# HMD_Button.net
KiCad netlist of a schematic drawn in Altium Designer
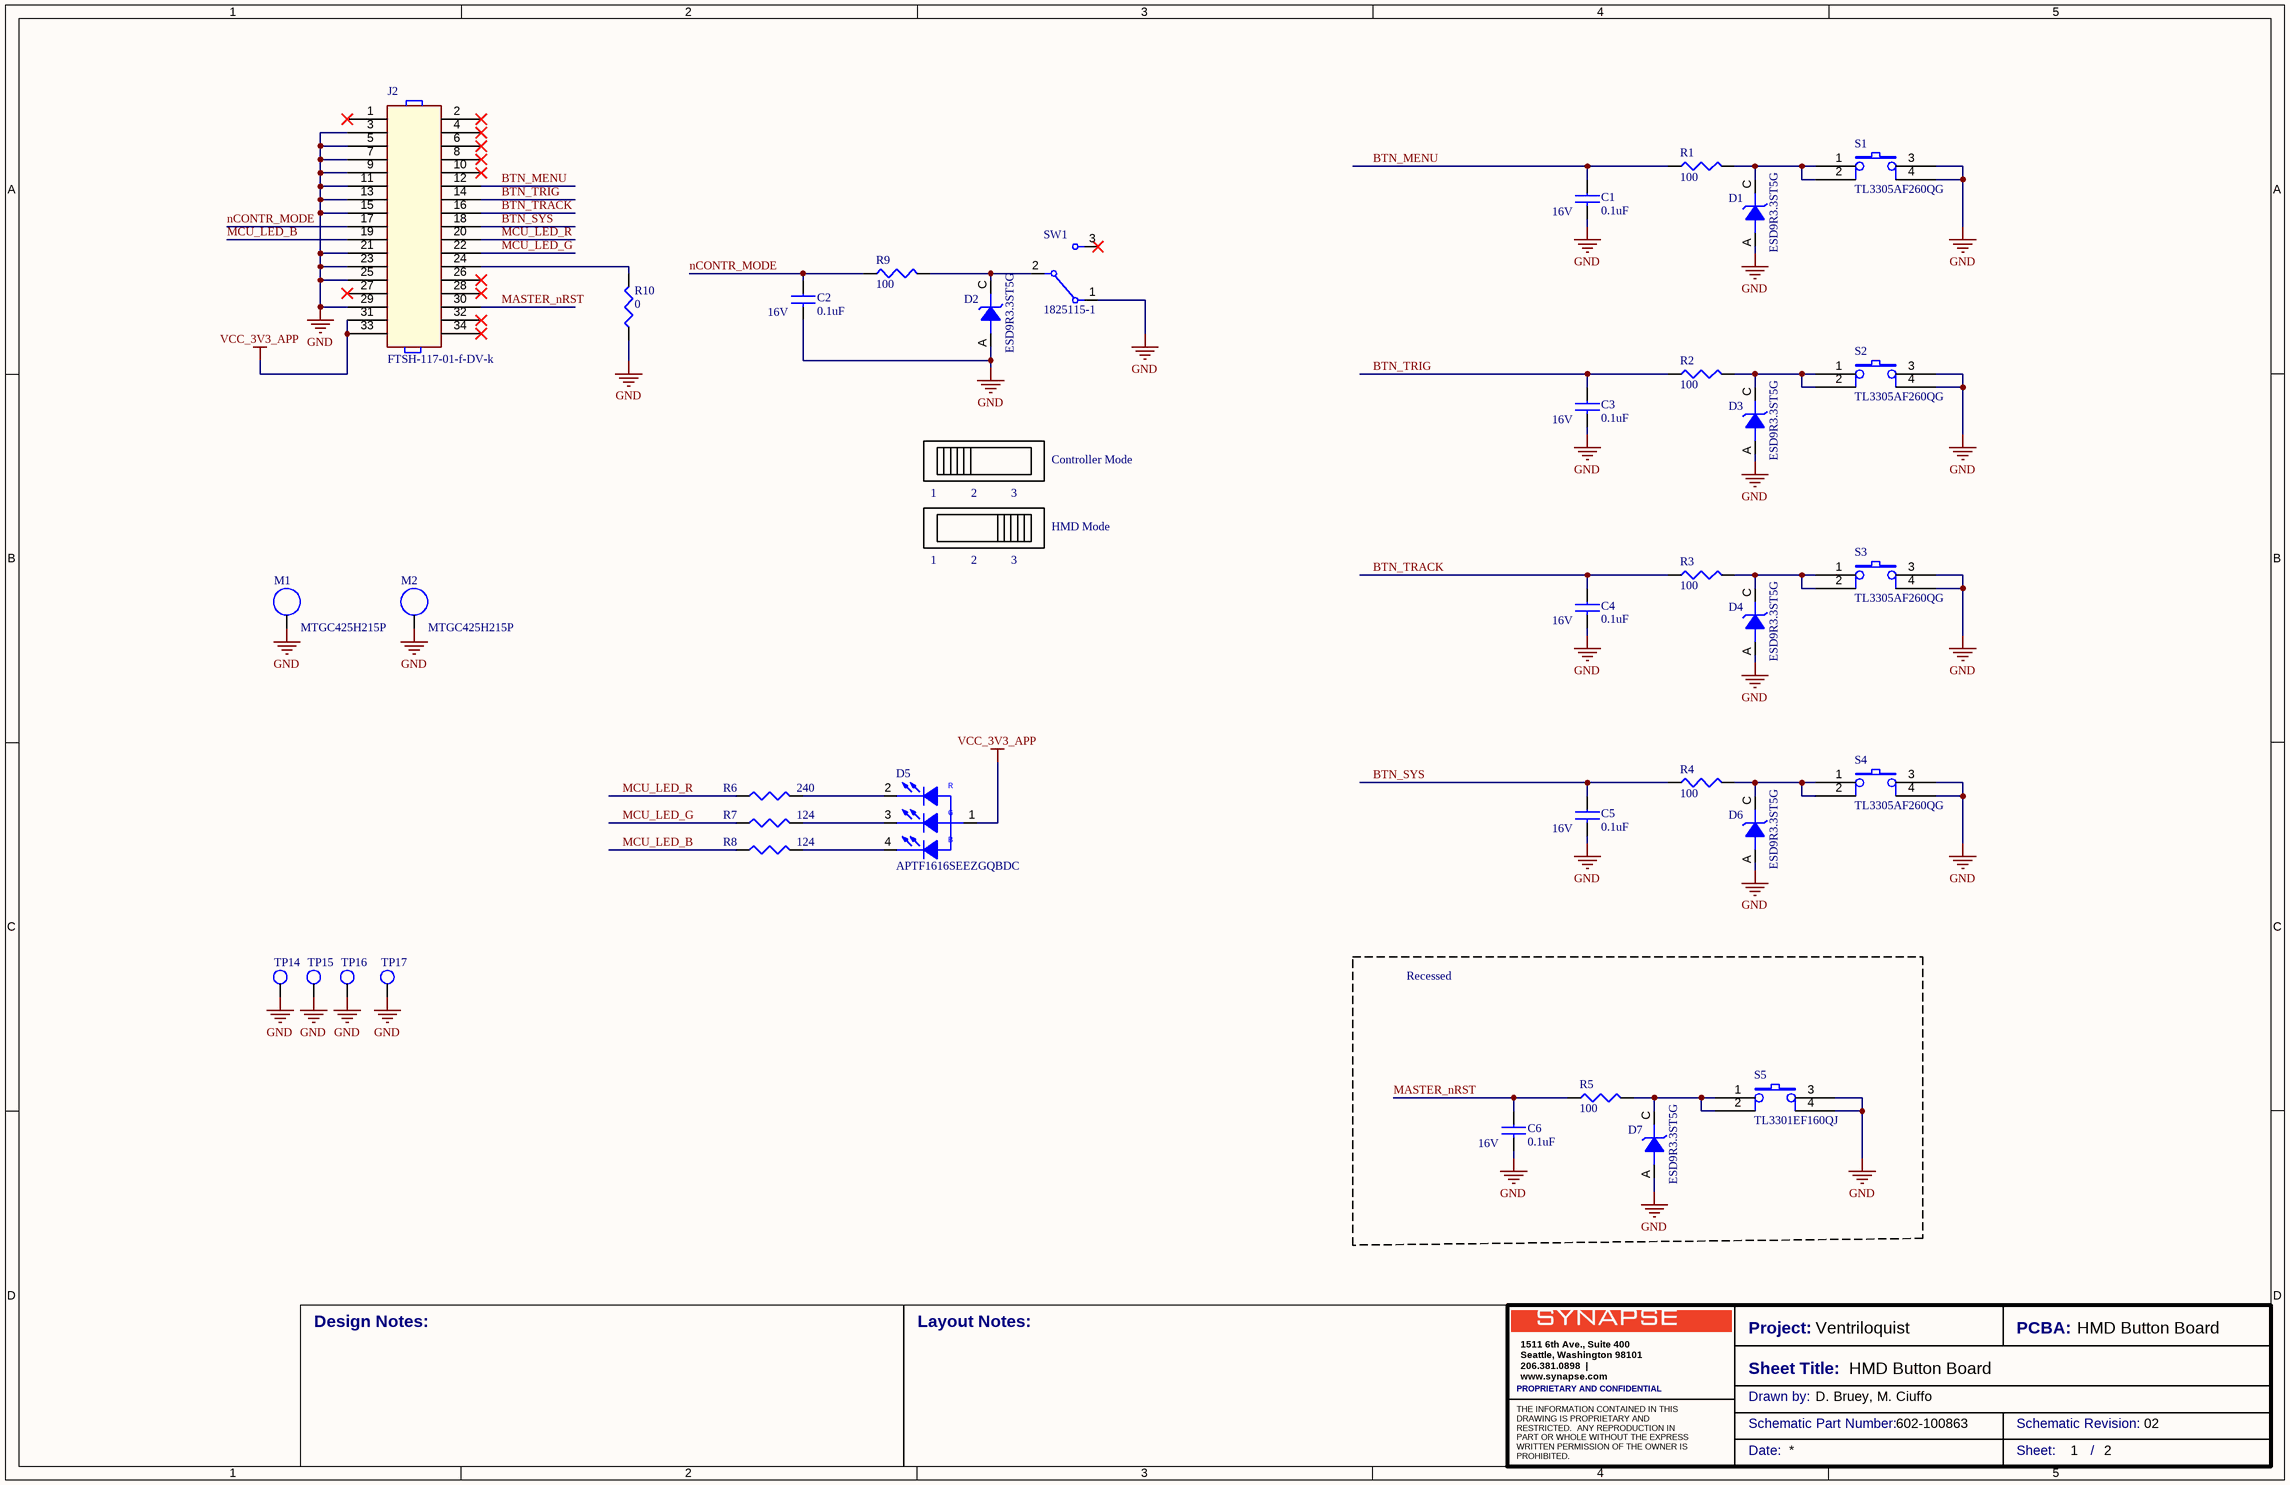
[diagram p0: HMD_Button.SchDoc]

(export (version "E")
  (design (tool "Eeschema 10.0.6"))
  (components
    (comp (ref "C1")
      (value "0.1uF")
      (footprint "0402-IPCsm_55")
      (description "CAP CER .1UF 16V X7R 0402")
      (fields (field (name "VOLTAGE") "16V") (field (name "MFG") "MURATA") (field (name "TOLERANCE") "10%"))
      (libsource (lib "SynapseLibrary") (part "CAP"))
    )
    (comp (ref "C2")
      (value "0.1uF")
      (footprint "0402-IPCsm_55")
      (description "CAP CER .1UF 16V X7R 0402")
      (fields (field (name "VOLTAGE") "16V") (field (name "MFG") "MURATA") (field (name "TOLERANCE") "10%"))
      (libsource (lib "SynapseLibrary") (part "CAP"))
    )
    (comp (ref "C3")
      (value "0.1uF")
      (footprint "0402-IPCsm_55")
      (description "CAP CER .1UF 16V X7R 0402")
      (fields (field (name "VOLTAGE") "16V") (field (name "MFG") "MURATA") (field (name "TOLERANCE") "10%"))
      (libsource (lib "SynapseLibrary") (part "CAP"))
    )
    (comp (ref "C4")
      (value "0.1uF")
      (footprint "0402-IPCsm_55")
      (description "CAP CER .1UF 16V X7R 0402")
      (fields (field (name "VOLTAGE") "16V") (field (name "MFG") "MURATA") (field (name "TOLERANCE") "10%"))
      (libsource (lib "SynapseLibrary") (part "CAP"))
    )
    (comp (ref "C5")
      (value "0.1uF")
      (footprint "0402-IPCsm_55")
      (description "CAP CER .1UF 16V X7R 0402")
      (fields (field (name "VOLTAGE") "16V") (field (name "MFG") "MURATA") (field (name "TOLERANCE") "10%"))
      (libsource (lib "SynapseLibrary") (part "CAP"))
    )
    (comp (ref "C6")
      (value "0.1uF")
      (footprint "0402-IPCsm_55")
      (description "CAP CER .1UF 16V X7R 0402")
      (fields (field (name "VOLTAGE") "16V") (field (name "MFG") "MURATA") (field (name "TOLERANCE") "10%"))
      (libsource (lib "SynapseLibrary") (part "CAP"))
    )
    (comp (ref "D1")
      (value "ESD9R3.3ST5G")
      (footprint "sod923-40")
      (description "TVS DIODE 3.3VWM 7.8VC SOD923")
      (fields (field (name "MFG") "On Semiconductor") (field (name "VOLTAGE") "3.3V"))
      (libsource (lib "SynapseLibrary") (part "TVS_UNI"))
    )
    (comp (ref "D2")
      (value "ESD9R3.3ST5G")
      (footprint "sod923-40")
      (description "TVS DIODE 3.3VWM 7.8VC SOD923")
      (fields (field (name "MFG") "On Semiconductor") (field (name "VOLTAGE") "3.3V"))
      (libsource (lib "SynapseLibrary") (part "TVS_UNI"))
    )
    (comp (ref "D3")
      (value "ESD9R3.3ST5G")
      (footprint "sod923-40")
      (description "TVS DIODE 3.3VWM 7.8VC SOD923")
      (fields (field (name "MFG") "On Semiconductor") (field (name "VOLTAGE") "3.3V"))
      (libsource (lib "SynapseLibrary") (part "TVS_UNI"))
    )
    (comp (ref "D4")
      (value "ESD9R3.3ST5G")
      (footprint "sod923-40")
      (description "TVS DIODE 3.3VWM 7.8VC SOD923")
      (fields (field (name "MFG") "On Semiconductor") (field (name "VOLTAGE") "3.3V"))
      (libsource (lib "SynapseLibrary") (part "TVS_UNI"))
    )
    (comp (ref "D5")
      (value "APTF1616SEEZGQBDC")
      (footprint "led_RBG_1p6x1p6_sm")
      (description "LED RGB CLEAR 0606 SMD")
      (fields (field (name "MFG") "Kingbright"))
      (libsource (lib "SynapseLibrary") (part "RGB_CA_HT-B3053FCH"))
    )
    (comp (ref "D6")
      (value "ESD9R3.3ST5G")
      (footprint "sod923-40")
      (description "TVS DIODE 3.3VWM 7.8VC SOD923")
      (fields (field (name "MFG") "On Semiconductor") (field (name "VOLTAGE") "3.3V"))
      (libsource (lib "SynapseLibrary") (part "TVS_UNI"))
    )
    (comp (ref "D7")
      (value "ESD9R3.3ST5G")
      (footprint "sod923-40")
      (description "TVS DIODE 3.3VWM 7.8VC SOD923")
      (fields (field (name "MFG") "On Semiconductor") (field (name "VOLTAGE") "3.3V"))
      (libsource (lib "SynapseLibrary") (part "TVS_UNI"))
    )
    (comp (ref "J2")
      (value "FTSH-117-01-f-DV-k")
      (footprint "FTSH-117-01-XXX-DV-K")
      (description "34 Positions Header, Shrouded Connector 0.050\" (1.27mm) Surface Mount Gold")
      (fields (field (name "MFG") "Samtec"))
      (libsource (lib "SynapseLibrary") (part "HEADER 17X2"))
    )
    (comp (ref "M1")
      (value "MTGC425H215P")
      (footprint "MTGC425H215P")
      (description "MTG, 4.25mm PAD, 2.15mm Plated Hole")
      (libsource (lib "SynapseLibrary") (part "MTG"))
    )
    (comp (ref "M2")
      (value "MTGC425H215P")
      (footprint "MTGC425H215P")
      (description "MTG, 4.25mm PAD, 2.15mm Plated Hole")
      (libsource (lib "SynapseLibrary") (part "MTG"))
    )
    (comp (ref "R1")
      (value "100")
      (footprint "0402-IPCsm_40")
      (description "RES 100 OHM 5% 0402 SMD")
      (fields (field (name "TOLERANCE") "5.00%") (field (name "MFG") "ROHM"))
      (libsource (lib "SynapseLibrary") (part "RES"))
    )
    (comp (ref "R2")
      (value "100")
      (footprint "0402-IPCsm_40")
      (description "RES 100 OHM 5% 0402 SMD")
      (fields (field (name "TOLERANCE") "5.00%") (field (name "MFG") "ROHM"))
      (libsource (lib "SynapseLibrary") (part "RES"))
    )
    (comp (ref "R3")
      (value "100")
      (footprint "0402-IPCsm_40")
      (description "RES 100 OHM 5% 0402 SMD")
      (fields (field (name "TOLERANCE") "5.00%") (field (name "MFG") "ROHM"))
      (libsource (lib "SynapseLibrary") (part "RES"))
    )
    (comp (ref "R4")
      (value "100")
      (footprint "0402-IPCsm_40")
      (description "RES 100 OHM 5% 0402 SMD")
      (fields (field (name "TOLERANCE") "5.00%") (field (name "MFG") "ROHM"))
      (libsource (lib "SynapseLibrary") (part "RES"))
    )
    (comp (ref "R5")
      (value "100")
      (footprint "0402-IPCsm_40")
      (description "RES 100 OHM 5% 0402 SMD")
      (fields (field (name "TOLERANCE") "5.00%") (field (name "MFG") "ROHM"))
      (libsource (lib "SynapseLibrary") (part "RES"))
    )
    (comp (ref "R6")
      (value "240")
      (footprint "0402-IPCsm_40")
      (description "RES 240 OHM 1/10W 1% 0402 SMD")
      (fields (field (name "TOLERANCE") "1%") (field (name "MFG") "Panasonic"))
      (libsource (lib "SynapseLibrary") (part "RES"))
    )
    (comp (ref "R7")
      (value "124")
      (footprint "0402-IPCsm_40")
      (description "RES SMD 124 OHM 1% 1/16W 0402")
      (fields (field (name "TOLERANCE") "1.00%") (field (name "MFG") "Yageo"))
      (libsource (lib "SynapseLibrary") (part "RES"))
    )
    (comp (ref "R8")
      (value "124")
      (footprint "0402-IPCsm_40")
      (description "RES SMD 124 OHM 1% 1/16W 0402")
      (fields (field (name "TOLERANCE") "1.00%") (field (name "MFG") "Yageo"))
      (libsource (lib "SynapseLibrary") (part "RES"))
    )
    (comp (ref "R9")
      (value "100")
      (footprint "0402-IPCsm_40")
      (description "RES 100 OHM 5% 0402 SMD")
      (fields (field (name "TOLERANCE") "5.00%") (field (name "MFG") "ROHM"))
      (libsource (lib "SynapseLibrary") (part "RES"))
    )
    (comp (ref "R10")
      (value "0")
      (footprint "0402-IPCsm_40")
      (description "RES 0.0 OHM 1/10W JUMP 0402 SMD")
      (fields (field (name "TOLERANCE") "5.00%") (field (name "MFG") "PANASONIC"))
      (libsource (lib "SynapseLibrary") (part "RES"))
    )
    (comp (ref "S1")
      (value "TL3305AF260QG")
      (footprint "SW_TL3305_G")
      (description "SWITCH TACTILE SPST-NO 50MA 12V")
      (fields (field (name "PART NUMBER") "TL3301AF260QG") (field (name "MANUFACTURER") "E-Switch"))
      (libsource (lib "SynapseLibrary") (part "ESWITCH_TL3301AF"))
    )
    (comp (ref "S2")
      (value "TL3305AF260QG")
      (footprint "SW_TL3305_G")
      (description "SWITCH TACTILE SPST-NO 50MA 12V")
      (fields (field (name "PART NUMBER") "TL3301AF260QG") (field (name "MANUFACTURER") "E-Switch"))
      (libsource (lib "SynapseLibrary") (part "ESWITCH_TL3301AF"))
    )
    (comp (ref "S3")
      (value "TL3305AF260QG")
      (footprint "SW_TL3305_G")
      (description "SWITCH TACTILE SPST-NO 50MA 12V")
      (fields (field (name "PART NUMBER") "TL3301AF260QG") (field (name "MANUFACTURER") "E-Switch"))
      (libsource (lib "SynapseLibrary") (part "ESWITCH_TL3301AF"))
    )
    (comp (ref "S4")
      (value "TL3305AF260QG")
      (footprint "SW_TL3305_G")
      (description "SWITCH TACTILE SPST-NO 50MA 12V")
      (fields (field (name "PART NUMBER") "TL3301AF260QG") (field (name "MANUFACTURER") "E-Switch"))
      (libsource (lib "SynapseLibrary") (part "ESWITCH_TL3301AF"))
    )
    (comp (ref "S5")
      (value "TL3301EF160QJ")
      (footprint "SW_TL3301_J")
      (description "SWITCH TACTILE SPST-NO 0.05A 12V")
      (fields (field (name "PART NUMBER") "TL3301AF260QG") (field (name "MANUFACTURER") "E-Switch"))
      (libsource (lib "SynapseLibrary") (part "ESWITCH_TL3301AF"))
    )
    (comp (ref "SW1")
      (value "1825115-1")
      (footprint "SW_3_TE_1825115")
      (description "SWITCH SLIDE SPDT 250MA 125V")
      (fields (field (name "MFG") "TE Connectivity"))
      (libsource (lib "SynapseLibrary") (part "SW_SLIDE_SPDT"))
    )
    (comp (ref "TP14")
      (value "tp-1mm")
      (footprint "TP-S100_SMT")
      (description "TESTPOINT, 1MM SMD, Square pad, Round SM opening")
      (fields (field (name "MFG") "NA"))
      (libsource (lib "SynapseLibrary") (part "tp_smt"))
    )
    (comp (ref "TP15")
      (value "tp-1mm")
      (footprint "TP-S100_SMT")
      (description "TESTPOINT, 1MM SMD, Square pad, Round SM opening")
      (fields (field (name "MFG") "NA"))
      (libsource (lib "SynapseLibrary") (part "tp_smt"))
    )
    (comp (ref "TP16")
      (value "tp-1mm")
      (footprint "TP-S100_SMT")
      (description "TESTPOINT, 1MM SMD, Square pad, Round SM opening")
      (fields (field (name "MFG") "NA"))
      (libsource (lib "SynapseLibrary") (part "tp_smt"))
    )
    (comp (ref "TP17")
      (value "tp-1mm")
      (footprint "TP-S100_SMT")
      (description "TESTPOINT, 1MM SMD, Square pad, Round SM opening")
      (fields (field (name "MFG") "NA"))
      (libsource (lib "SynapseLibrary") (part "tp_smt"))
    )
  )
  (nets
    (net (code "1") (name "/BTN_MENU") (class "Default")
      (node (ref "C1") (pin "1") (pinfunction "1_1") (pintype "passive"))
      (node (ref "J2") (pin "12") (pinfunction "12_12") (pintype "passive"))
      (node (ref "R1") (pin "1") (pinfunction "1_1") (pintype "passive"))
    )
    (net (code "2") (name "/BTN_SYS") (class "Default")
      (node (ref "C5") (pin "1") (pinfunction "1_1") (pintype "passive"))
      (node (ref "J2") (pin "18") (pinfunction "18_18") (pintype "passive"))
      (node (ref "R4") (pin "1") (pinfunction "1_1") (pintype "passive"))
    )
    (net (code "3") (name "/BTN_TRACK") (class "Default")
      (node (ref "C4") (pin "1") (pinfunction "1_1") (pintype "passive"))
      (node (ref "J2") (pin "16") (pinfunction "16_16") (pintype "passive"))
      (node (ref "R3") (pin "1") (pinfunction "1_1") (pintype "passive"))
    )
    (net (code "4") (name "/BTN_TRIG") (class "Default")
      (node (ref "C3") (pin "1") (pinfunction "1_1") (pintype "passive"))
      (node (ref "J2") (pin "14") (pinfunction "14_14") (pintype "passive"))
      (node (ref "R2") (pin "1") (pinfunction "1_1") (pintype "passive"))
    )
    (net (code "5") (name "/MASTER_nRST") (class "Default")
      (node (ref "C6") (pin "1") (pinfunction "1_1") (pintype "passive"))
      (node (ref "J2") (pin "30") (pinfunction "30_30") (pintype "passive"))
      (node (ref "R5") (pin "1") (pinfunction "1_1") (pintype "passive"))
    )
    (net (code "6") (name "/MCU_LED_B") (class "Default")
      (node (ref "J2") (pin "19") (pinfunction "19_19") (pintype "passive"))
      (node (ref "R8") (pin "1") (pinfunction "1_1") (pintype "passive"))
    )
    (net (code "7") (name "/MCU_LED_G") (class "Default")
      (node (ref "J2") (pin "22") (pinfunction "22_22") (pintype "passive"))
      (node (ref "R7") (pin "1") (pinfunction "1_1") (pintype "passive"))
    )
    (net (code "8") (name "/MCU_LED_R") (class "Default")
      (node (ref "J2") (pin "20") (pinfunction "20_20") (pintype "passive"))
      (node (ref "R6") (pin "1") (pinfunction "1_1") (pintype "passive"))
    )
    (net (code "9") (name "/nCONTR_MODE") (class "Default")
      (node (ref "C2") (pin "1") (pinfunction "1_1") (pintype "passive"))
      (node (ref "J2") (pin "17") (pinfunction "17_17") (pintype "passive"))
      (node (ref "R9") (pin "1") (pinfunction "1_1") (pintype "passive"))
    )
    (net (code "10") (name "GND") (class "Default")
      (node (ref "C1") (pin "2") (pinfunction "2_2") (pintype "passive"))
      (node (ref "C2") (pin "2") (pinfunction "2_2") (pintype "passive"))
      (node (ref "C3") (pin "2") (pinfunction "2_2") (pintype "passive"))
      (node (ref "C4") (pin "2") (pinfunction "2_2") (pintype "passive"))
      (node (ref "C5") (pin "2") (pinfunction "2_2") (pintype "passive"))
      (node (ref "C6") (pin "2") (pinfunction "2_2") (pintype "passive"))
      (node (ref "D1") (pin "A") (pinfunction "A_A") (pintype "passive"))
      (node (ref "D2") (pin "A") (pinfunction "A_A") (pintype "passive"))
      (node (ref "D3") (pin "A") (pinfunction "A_A") (pintype "passive"))
      (node (ref "D4") (pin "A") (pinfunction "A_A") (pintype "passive"))
      (node (ref "D6") (pin "A") (pinfunction "A_A") (pintype "passive"))
      (node (ref "D7") (pin "A") (pinfunction "A_A") (pintype "passive"))
      (node (ref "J2") (pin "11") (pinfunction "11_11") (pintype "passive"))
      (node (ref "J2") (pin "13") (pinfunction "13_13") (pintype "passive"))
      (node (ref "J2") (pin "15") (pinfunction "15_15") (pintype "passive"))
      (node (ref "J2") (pin "21") (pinfunction "21_21") (pintype "passive"))
      (node (ref "J2") (pin "23") (pinfunction "23_23") (pintype "passive"))
      (node (ref "J2") (pin "25") (pinfunction "25_25") (pintype "passive"))
      (node (ref "J2") (pin "29") (pinfunction "29_29") (pintype "passive"))
      (node (ref "J2") (pin "3") (pinfunction "3_3") (pintype "passive"))
      (node (ref "J2") (pin "5") (pinfunction "5_5") (pintype "passive"))
      (node (ref "J2") (pin "7") (pinfunction "7_7") (pintype "passive"))
      (node (ref "J2") (pin "9") (pinfunction "9_9") (pintype "passive"))
      (node (ref "M1") (pin "1") (pinfunction "1_1") (pintype "passive"))
      (node (ref "M2") (pin "1") (pinfunction "1_1") (pintype "passive"))
      (node (ref "R10") (pin "1") (pinfunction "1_1") (pintype "passive"))
      (node (ref "S1") (pin "3") (pinfunction "3_3") (pintype "passive"))
      (node (ref "S1") (pin "4") (pinfunction "4_4") (pintype "passive"))
      (node (ref "S2") (pin "3") (pinfunction "3_3") (pintype "passive"))
      (node (ref "S2") (pin "4") (pinfunction "4_4") (pintype "passive"))
      (node (ref "S3") (pin "3") (pinfunction "3_3") (pintype "passive"))
      (node (ref "S3") (pin "4") (pinfunction "4_4") (pintype "passive"))
      (node (ref "S4") (pin "3") (pinfunction "3_3") (pintype "passive"))
      (node (ref "S4") (pin "4") (pinfunction "4_4") (pintype "passive"))
      (node (ref "S5") (pin "3") (pinfunction "3_3") (pintype "passive"))
      (node (ref "S5") (pin "4") (pinfunction "4_4") (pintype "passive"))
      (node (ref "SW1") (pin "1") (pinfunction "1_1") (pintype "passive"))
      (node (ref "TP14") (pin "1") (pinfunction "TP_1") (pintype "passive"))
      (node (ref "TP15") (pin "1") (pinfunction "TP_1") (pintype "passive"))
      (node (ref "TP16") (pin "1") (pinfunction "TP_1") (pintype "passive"))
      (node (ref "TP17") (pin "1") (pinfunction "TP_1") (pintype "passive"))
    )
    (net (code "11") (name "Net-(D1-PadC)") (class "Default")
      (node (ref "D1") (pin "C") (pinfunction "C_C") (pintype "passive"))
      (node (ref "R1") (pin "2") (pinfunction "2_2") (pintype "passive"))
      (node (ref "S1") (pin "1") (pinfunction "1_1") (pintype "passive"))
      (node (ref "S1") (pin "2") (pinfunction "2_2") (pintype "passive"))
    )
    (net (code "12") (name "Net-(D2-PadC)") (class "Default")
      (node (ref "D2") (pin "C") (pinfunction "C_C") (pintype "passive"))
      (node (ref "R9") (pin "2") (pinfunction "2_2") (pintype "passive"))
      (node (ref "SW1") (pin "2") (pinfunction "2_2") (pintype "passive"))
    )
    (net (code "13") (name "Net-(D3-PadC)") (class "Default")
      (node (ref "D3") (pin "C") (pinfunction "C_C") (pintype "passive"))
      (node (ref "R2") (pin "2") (pinfunction "2_2") (pintype "passive"))
      (node (ref "S2") (pin "1") (pinfunction "1_1") (pintype "passive"))
      (node (ref "S2") (pin "2") (pinfunction "2_2") (pintype "passive"))
    )
    (net (code "14") (name "Net-(D4-PadC)") (class "Default")
      (node (ref "D4") (pin "C") (pinfunction "C_C") (pintype "passive"))
      (node (ref "R3") (pin "2") (pinfunction "2_2") (pintype "passive"))
      (node (ref "S3") (pin "1") (pinfunction "1_1") (pintype "passive"))
      (node (ref "S3") (pin "2") (pinfunction "2_2") (pintype "passive"))
    )
    (net (code "15") (name "Net-(D5-B)") (class "Default")
      (node (ref "D5") (pin "4") (pinfunction "B_4") (pintype "passive"))
      (node (ref "R8") (pin "2") (pinfunction "2_2") (pintype "passive"))
    )
    (net (code "16") (name "Net-(D5-G)") (class "Default")
      (node (ref "D5") (pin "3") (pinfunction "G_3") (pintype "passive"))
      (node (ref "R7") (pin "2") (pinfunction "2_2") (pintype "passive"))
    )
    (net (code "17") (name "Net-(D5-R)") (class "Default")
      (node (ref "D5") (pin "2") (pinfunction "R_2") (pintype "passive"))
      (node (ref "R6") (pin "2") (pinfunction "2_2") (pintype "passive"))
    )
    (net (code "18") (name "Net-(D6-PadC)") (class "Default")
      (node (ref "D6") (pin "C") (pinfunction "C_C") (pintype "passive"))
      (node (ref "R4") (pin "2") (pinfunction "2_2") (pintype "passive"))
      (node (ref "S4") (pin "1") (pinfunction "1_1") (pintype "passive"))
      (node (ref "S4") (pin "2") (pinfunction "2_2") (pintype "passive"))
    )
    (net (code "19") (name "Net-(D7-PadC)") (class "Default")
      (node (ref "D7") (pin "C") (pinfunction "C_C") (pintype "passive"))
      (node (ref "R5") (pin "2") (pinfunction "2_2") (pintype "passive"))
      (node (ref "S5") (pin "1") (pinfunction "1_1") (pintype "passive"))
      (node (ref "S5") (pin "2") (pinfunction "2_2") (pintype "passive"))
    )
    (net (code "20") (name "Net-(J2-Pad24)") (class "Default")
      (node (ref "J2") (pin "24") (pinfunction "24_24") (pintype "passive"))
      (node (ref "R10") (pin "2") (pinfunction "2_2") (pintype "passive"))
    )
    (net (code "21") (name "VCC_3V3_APP") (class "Default")
      (node (ref "D5") (pin "1") (pinfunction "ANODE_1") (pintype "passive"))
      (node (ref "J2") (pin "31") (pinfunction "31_31") (pintype "passive"))
      (node (ref "J2") (pin "33") (pinfunction "33_33") (pintype "passive"))
    )
    (net (code "22") (name "unconnected-(J2-Pad1)") (class "Default")
      (node (ref "J2") (pin "1") (pinfunction "1_1") (pintype "passive+no_connect"))
    )
    (net (code "23") (name "unconnected-(J2-Pad2)") (class "Default")
      (node (ref "J2") (pin "2") (pinfunction "2_2") (pintype "passive+no_connect"))
    )
    (net (code "24") (name "unconnected-(J2-Pad4)") (class "Default")
      (node (ref "J2") (pin "4") (pinfunction "4_4") (pintype "passive+no_connect"))
    )
    (net (code "25") (name "unconnected-(J2-Pad6)") (class "Default")
      (node (ref "J2") (pin "6") (pinfunction "6_6") (pintype "passive+no_connect"))
    )
    (net (code "26") (name "unconnected-(J2-Pad8)") (class "Default")
      (node (ref "J2") (pin "8") (pinfunction "8_8") (pintype "passive+no_connect"))
    )
    (net (code "27") (name "unconnected-(J2-Pad10)") (class "Default")
      (node (ref "J2") (pin "10") (pinfunction "10_10") (pintype "passive+no_connect"))
    )
    (net (code "28") (name "unconnected-(J2-Pad26)") (class "Default")
      (node (ref "J2") (pin "26") (pinfunction "26_26") (pintype "passive+no_connect"))
    )
    (net (code "29") (name "unconnected-(J2-Pad27)") (class "Default")
      (node (ref "J2") (pin "27") (pinfunction "27_27") (pintype "passive+no_connect"))
    )
    (net (code "30") (name "unconnected-(J2-Pad28)") (class "Default")
      (node (ref "J2") (pin "28") (pinfunction "28_28") (pintype "passive+no_connect"))
    )
    (net (code "31") (name "unconnected-(J2-Pad32)") (class "Default")
      (node (ref "J2") (pin "32") (pinfunction "32_32") (pintype "passive+no_connect"))
    )
    (net (code "32") (name "unconnected-(J2-Pad34)") (class "Default")
      (node (ref "J2") (pin "34") (pinfunction "34_34") (pintype "passive+no_connect"))
    )
    (net (code "33") (name "unconnected-(SW1-Pad3)") (class "Default")
      (node (ref "SW1") (pin "3") (pinfunction "3_3") (pintype "passive+no_connect"))
    )
  )
)
